# PCB_Tester2_V1_0.net
KiCad netlist of a schematic drawn in EAGLE
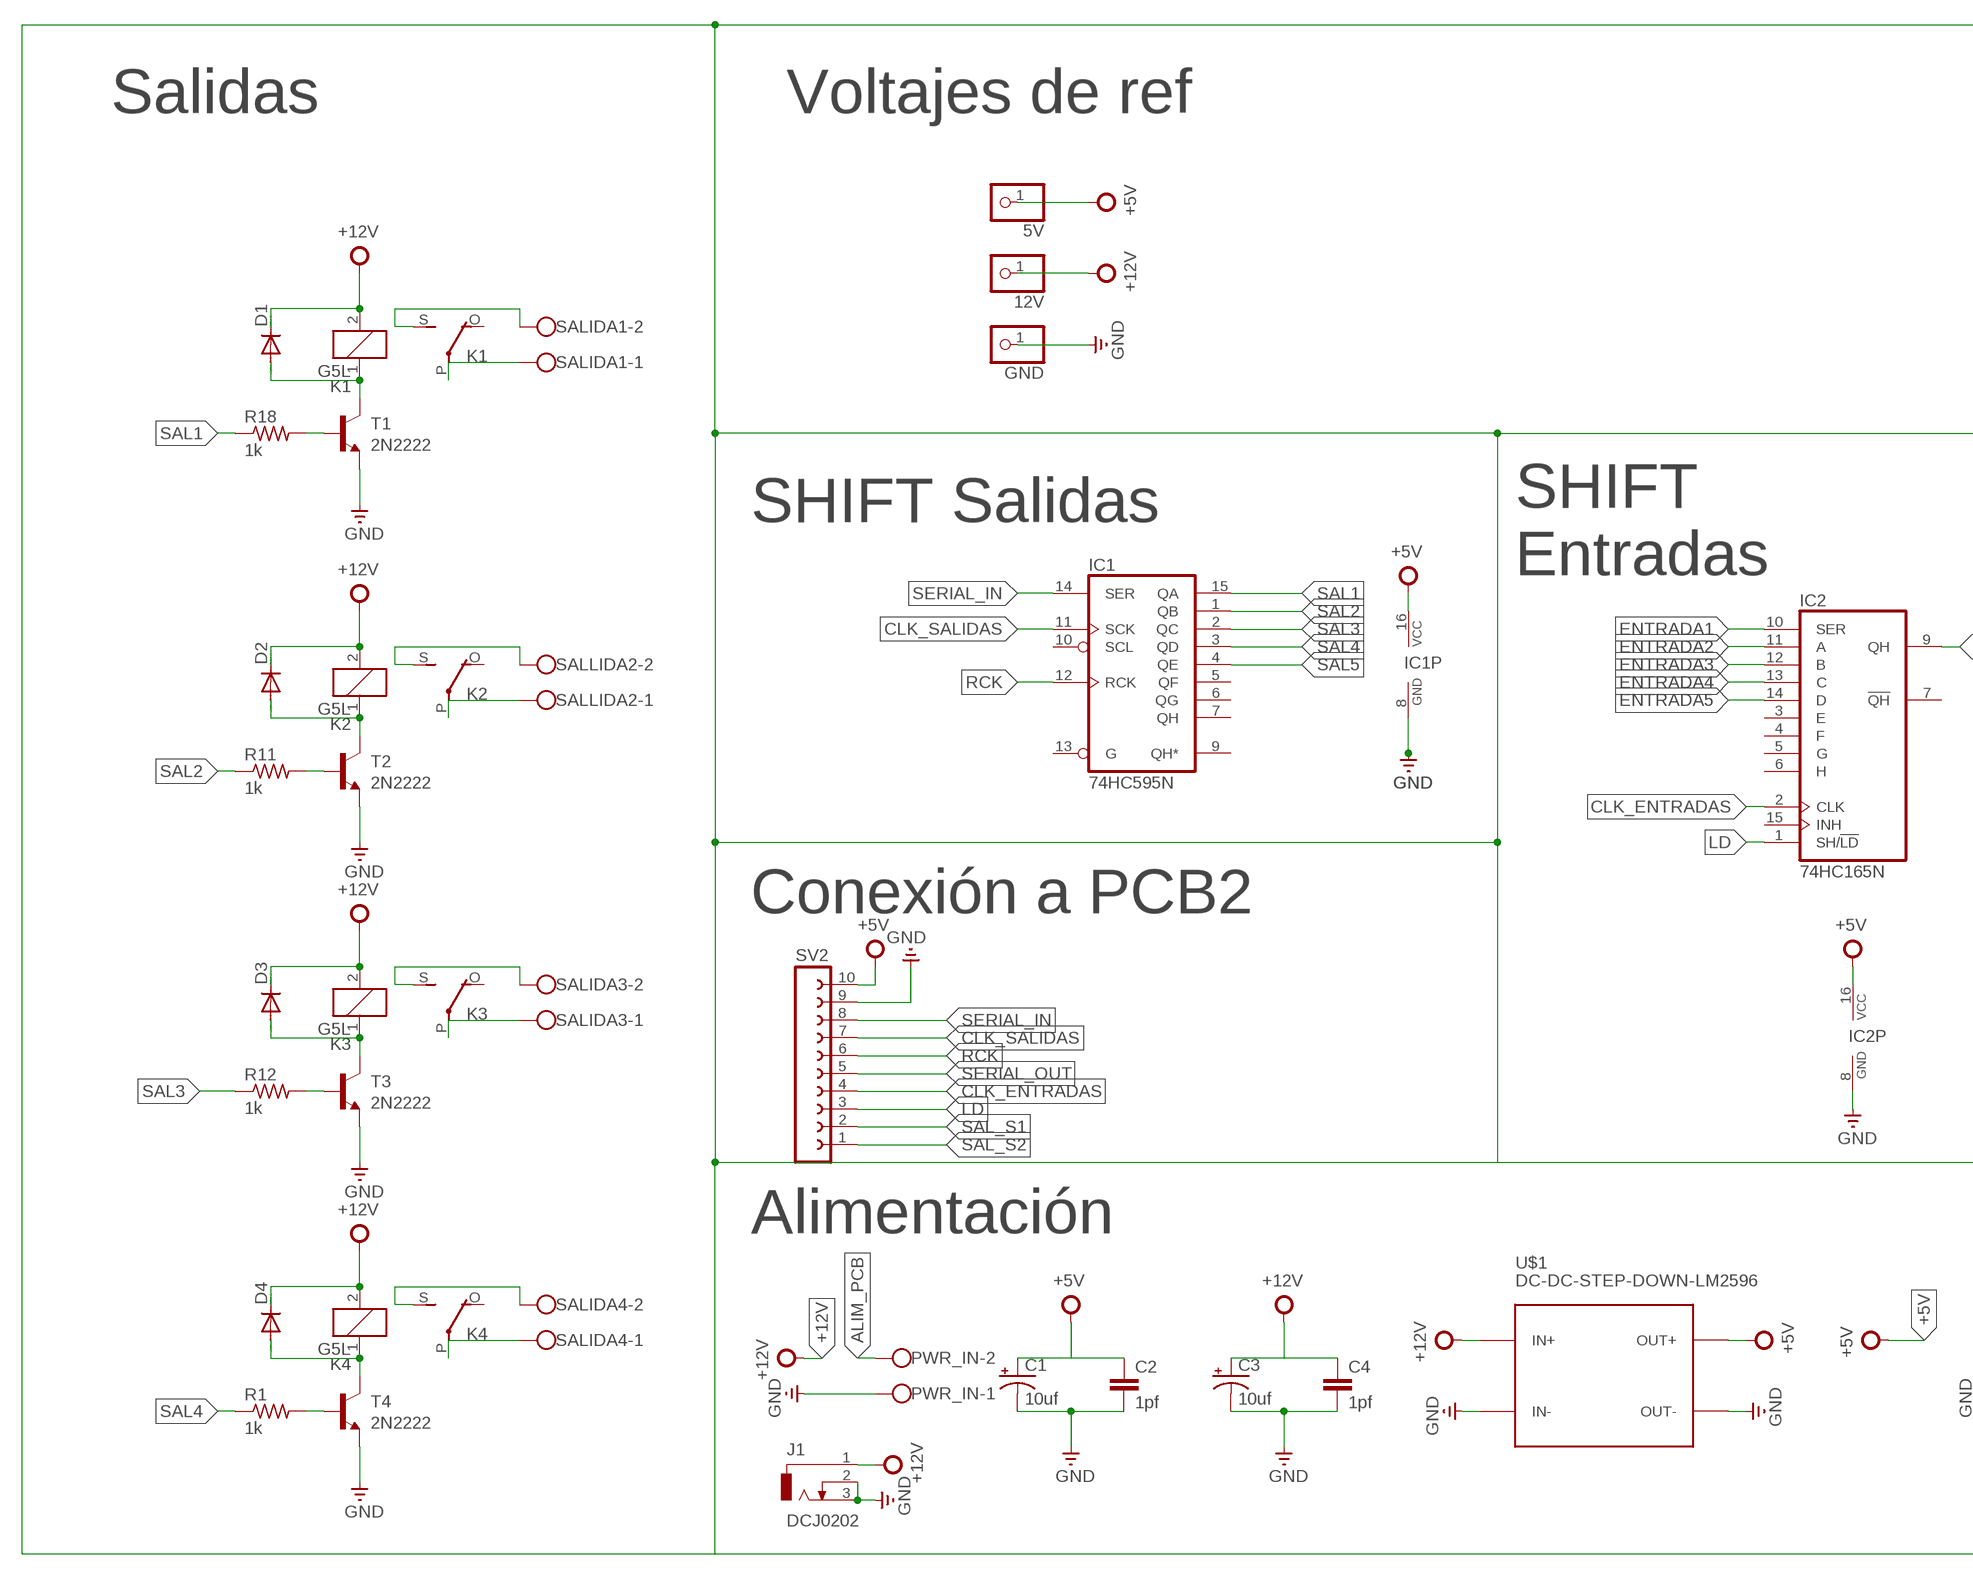
[diagram p0: schematic, sheet 1, part 1 of 2]
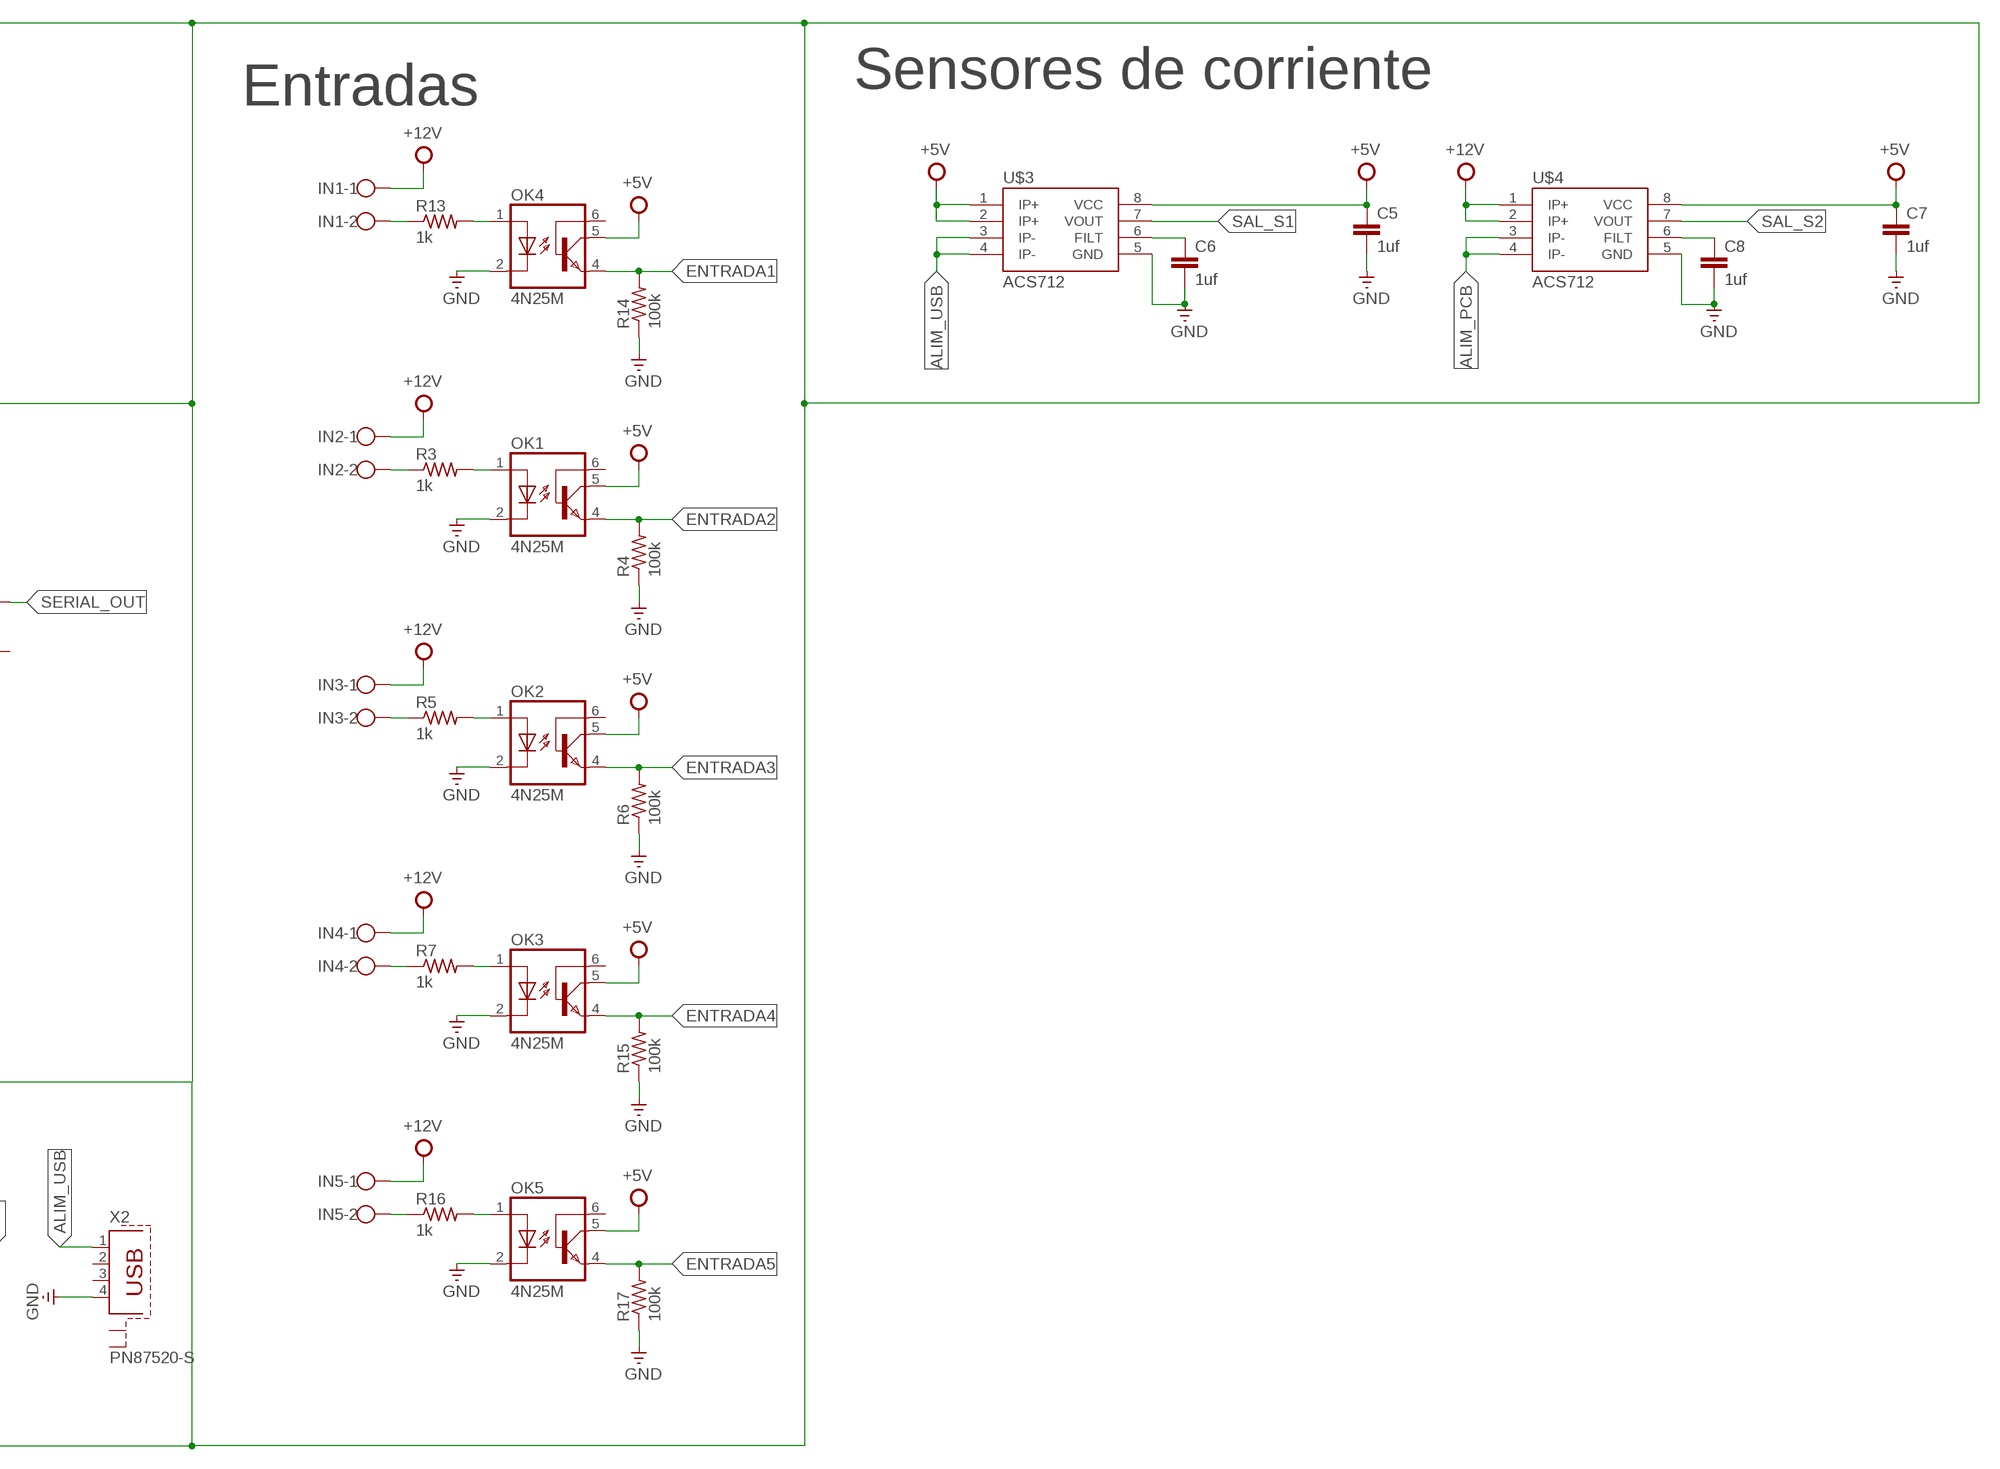
[diagram p1: schematic, sheet 1, part 2 of 2]

(export (version "E")
  (design (tool "Eeschema 10.0.6"))
  (components
    (comp (ref "5V")
      (value "PINHD-1X1")
      (footprint "eagle-import:1X01")
      (libsource (lib "eagle-import") (part "PINHD-1X1"))
    )
    (comp (ref "12V")
      (value "PINHD-1X1")
      (footprint "eagle-import:1X01")
      (libsource (lib "eagle-import") (part "PINHD-1X1"))
    )
    (comp (ref "C1")
      (value "10uf")
      (footprint "eagle-import:E2,5-6")
      (libsource (lib "eagle-import") (part "CPOL-USE2.5-6"))
    )
    (comp (ref "C2")
      (value "1pf")
      (footprint "eagle-import:C2.5-3")
      (libsource (lib "eagle-import") (part "C2,5-3"))
    )
    (comp (ref "C3")
      (value "10uf")
      (footprint "eagle-import:E2,5-6")
      (libsource (lib "eagle-import") (part "CPOL-USE2.5-6"))
    )
    (comp (ref "C4")
      (value "1pf")
      (footprint "eagle-import:C2.5-3")
      (libsource (lib "eagle-import") (part "C2,5-3"))
    )
    (comp (ref "C5")
      (value "1uf")
      (footprint "eagle-import:C2.5-3")
      (libsource (lib "eagle-import") (part "C2,5-3"))
    )
    (comp (ref "C6")
      (value "1uf")
      (footprint "eagle-import:C2.5-3")
      (libsource (lib "eagle-import") (part "C2,5-3"))
    )
    (comp (ref "C7")
      (value "1uf")
      (footprint "eagle-import:C2.5-3")
      (libsource (lib "eagle-import") (part "C2,5-3"))
    )
    (comp (ref "C8")
      (value "1uf")
      (footprint "eagle-import:C2.5-3")
      (libsource (lib "eagle-import") (part "C2,5-3"))
    )
    (comp (ref "D1")
      (value "1N4148DO35-7")
      (footprint "eagle-import:DO35-7")
      (libsource (lib "eagle-import") (part "1N4148DO35-7"))
    )
    (comp (ref "D2")
      (value "1N4148DO35-7")
      (footprint "eagle-import:DO35-7")
      (libsource (lib "eagle-import") (part "1N4148DO35-7"))
    )
    (comp (ref "D3")
      (value "1N4148DO35-7")
      (footprint "eagle-import:DO35-7")
      (libsource (lib "eagle-import") (part "1N4148DO35-7"))
    )
    (comp (ref "D4")
      (value "1N4148DO35-7")
      (footprint "eagle-import:DO35-7")
      (libsource (lib "eagle-import") (part "1N4148DO35-7"))
    )
    (comp (ref "GND")
      (value "PINHD-1X1")
      (footprint "eagle-import:1X01")
      (libsource (lib "eagle-import") (part "PINHD-1X1"))
    )
    (comp (ref "IC1")
      (value "74HC595N")
      (footprint "eagle-import:DIL16")
      (libsource (lib "eagle-import") (part "74595NHC"))
    )
    (comp (ref "IC2")
      (value "74HC165N")
      (footprint "eagle-import:DIL16")
      (libsource (lib "eagle-import") (part "74165NHC"))
    )
    (comp (ref "IN1")
      (value "W237-102")
      (footprint "eagle-import:W237-102")
      (fields (field (name "MPN") "237-102"))
      (libsource (lib "eagle-import") (part "W237-102"))
    )
    (comp (ref "IN2")
      (value "W237-102")
      (footprint "eagle-import:W237-102")
      (fields (field (name "MPN") "237-102"))
      (libsource (lib "eagle-import") (part "W237-102"))
    )
    (comp (ref "IN3")
      (value "W237-102")
      (footprint "eagle-import:W237-102")
      (fields (field (name "MPN") "237-102"))
      (libsource (lib "eagle-import") (part "W237-102"))
    )
    (comp (ref "IN4")
      (value "W237-102")
      (footprint "eagle-import:W237-102")
      (fields (field (name "MPN") "237-102"))
      (libsource (lib "eagle-import") (part "W237-102"))
    )
    (comp (ref "IN5")
      (value "W237-102")
      (footprint "eagle-import:W237-102")
      (fields (field (name "MPN") "237-102"))
      (libsource (lib "eagle-import") (part "W237-102"))
    )
    (comp (ref "J1")
      (value "DCJ0202")
      (footprint "eagle-import:DCJ0202")
      (libsource (lib "eagle-import") (part "DCJ0202"))
    )
    (comp (ref "K1")
      (value "G5L")
      (footprint "eagle-import:G5LE")
      (libsource (lib "eagle-import") (part "G5L"))
    )
    (comp (ref "K2")
      (value "G5L")
      (footprint "eagle-import:G5LE")
      (libsource (lib "eagle-import") (part "G5L"))
    )
    (comp (ref "K3")
      (value "G5L")
      (footprint "eagle-import:G5LE")
      (libsource (lib "eagle-import") (part "G5L"))
    )
    (comp (ref "K4")
      (value "G5L")
      (footprint "eagle-import:G5LE")
      (libsource (lib "eagle-import") (part "G5L"))
    )
    (comp (ref "OK1")
      (value "4N25M")
      (footprint "eagle-import:DIL06")
      (fields (field (name "MPN") "4N25-M"))
      (libsource (lib "eagle-import") (part "4N?M25"))
    )
    (comp (ref "OK2")
      (value "4N25M")
      (footprint "eagle-import:DIL06")
      (fields (field (name "MPN") "4N25-M"))
      (libsource (lib "eagle-import") (part "4N?M25"))
    )
    (comp (ref "OK3")
      (value "4N25M")
      (footprint "eagle-import:DIL06")
      (fields (field (name "MPN") "4N25-M"))
      (libsource (lib "eagle-import") (part "4N?M25"))
    )
    (comp (ref "OK4")
      (value "4N25M")
      (footprint "eagle-import:DIL06")
      (fields (field (name "MPN") "4N25-M"))
      (libsource (lib "eagle-import") (part "4N?M25"))
    )
    (comp (ref "OK5")
      (value "4N25M")
      (footprint "eagle-import:DIL06")
      (fields (field (name "MPN") "4N25-M"))
      (libsource (lib "eagle-import") (part "4N?M25"))
    )
    (comp (ref "PWR_IN")
      (value "W237-102")
      (footprint "eagle-import:W237-102")
      (fields (field (name "MPN") "237-102"))
      (libsource (lib "eagle-import") (part "W237-102"))
    )
    (comp (ref "R1")
      (value "1k")
      (footprint "eagle-import:0207_7")
      (libsource (lib "eagle-import") (part "R-US_0207/7"))
    )
    (comp (ref "R3")
      (value "1k")
      (footprint "eagle-import:0207_7")
      (libsource (lib "eagle-import") (part "R-US_0207/7"))
    )
    (comp (ref "R4")
      (value "100k")
      (footprint "eagle-import:0207_7")
      (libsource (lib "eagle-import") (part "R-US_0207/7"))
    )
    (comp (ref "R5")
      (value "1k")
      (footprint "eagle-import:0207_7")
      (libsource (lib "eagle-import") (part "R-US_0207/7"))
    )
    (comp (ref "R6")
      (value "100k")
      (footprint "eagle-import:0207_7")
      (libsource (lib "eagle-import") (part "R-US_0207/7"))
    )
    (comp (ref "R7")
      (value "1k")
      (footprint "eagle-import:0207_7")
      (libsource (lib "eagle-import") (part "R-US_0207/7"))
    )
    (comp (ref "R11")
      (value "1k")
      (footprint "eagle-import:0207_7")
      (libsource (lib "eagle-import") (part "R-US_0207/7"))
    )
    (comp (ref "R12")
      (value "1k")
      (footprint "eagle-import:0207_7")
      (libsource (lib "eagle-import") (part "R-US_0207/7"))
    )
    (comp (ref "R13")
      (value "1k")
      (footprint "eagle-import:0207_7")
      (libsource (lib "eagle-import") (part "R-US_0207/7"))
    )
    (comp (ref "R14")
      (value "100k")
      (footprint "eagle-import:0207_7")
      (libsource (lib "eagle-import") (part "R-US_0207/7"))
    )
    (comp (ref "R15")
      (value "100k")
      (footprint "eagle-import:0207_7")
      (libsource (lib "eagle-import") (part "R-US_0207/7"))
    )
    (comp (ref "R16")
      (value "1k")
      (footprint "eagle-import:0207_7")
      (libsource (lib "eagle-import") (part "R-US_0207/7"))
    )
    (comp (ref "R17")
      (value "100k")
      (footprint "eagle-import:0207_7")
      (libsource (lib "eagle-import") (part "R-US_0207/7"))
    )
    (comp (ref "R18")
      (value "1k")
      (footprint "eagle-import:0207_7")
      (libsource (lib "eagle-import") (part "R-US_0207/7"))
    )
    (comp (ref "SALIDA1")
      (value "W237-102")
      (footprint "eagle-import:W237-102")
      (fields (field (name "MPN") "237-102"))
      (libsource (lib "eagle-import") (part "W237-102"))
    )
    (comp (ref "SALIDA3")
      (value "W237-102")
      (footprint "eagle-import:W237-102")
      (fields (field (name "MPN") "237-102"))
      (libsource (lib "eagle-import") (part "W237-102"))
    )
    (comp (ref "SALIDA4")
      (value "W237-102")
      (footprint "eagle-import:W237-102")
      (fields (field (name "MPN") "237-102"))
      (libsource (lib "eagle-import") (part "W237-102"))
    )
    (comp (ref "SALLIDA2")
      (value "W237-102")
      (footprint "eagle-import:W237-102")
      (fields (field (name "MPN") "237-102"))
      (libsource (lib "eagle-import") (part "W237-102"))
    )
    (comp (ref "SV2")
      (value "FE10-1")
      (footprint "eagle-import:FE10")
      (libsource (lib "eagle-import") (part "FE10-1"))
    )
    (comp (ref "T1")
      (value "2N2222")
      (footprint "eagle-import:TO18")
      (libsource (lib "eagle-import") (part "2N2222"))
    )
    (comp (ref "T2")
      (value "2N2222")
      (footprint "eagle-import:TO18")
      (libsource (lib "eagle-import") (part "2N2222"))
    )
    (comp (ref "T3")
      (value "2N2222")
      (footprint "eagle-import:TO18")
      (libsource (lib "eagle-import") (part "2N2222"))
    )
    (comp (ref "T4")
      (value "2N2222")
      (footprint "eagle-import:TO18")
      (libsource (lib "eagle-import") (part "2N2222"))
    )
    (comp (ref "U$1")
      (value "DC-DC-STEP-DOWN-LM2596")
      (footprint "eagle-import:DC-DC-STEP-DOWN-LM2596")
      (libsource (lib "eagle-import") (part "DC-DC-STEP-DOWN-LM2596"))
    )
    (comp (ref "U$3")
      (value "ACS712")
      (footprint "eagle-import:SO08")
      (libsource (lib "eagle-import") (part "ACS712"))
    )
    (comp (ref "U$4")
      (value "ACS712")
      (footprint "eagle-import:SO08")
      (libsource (lib "eagle-import") (part "ACS712"))
    )
    (comp (ref "X2")
      (value "PN87520-S")
      (footprint "eagle-import:PN87520-S")
      (libsource (lib "eagle-import") (part "PN87520-S"))
    )
  )
  (nets
    (net (code "1") (name "+5V") (class "Default")
      (node (ref "5V") (pin "1") (pinfunction "1_1") (pintype "passive"))
      (node (ref "C1") (pin "+") (pinfunction "+_+") (pintype "passive"))
      (node (ref "C2") (pin "1") (pinfunction "1_1") (pintype "passive"))
      (node (ref "C5") (pin "1") (pinfunction "1_1") (pintype "passive"))
      (node (ref "C7") (pin "1") (pinfunction "1_1") (pintype "passive"))
      (node (ref "IC1") (pin "16") (pinfunction "VCC_16") (pintype "power_in"))
      (node (ref "IC2") (pin "16") (pinfunction "VCC_16") (pintype "power_in"))
      (node (ref "OK1") (pin "5") (pinfunction "COL_5") (pintype "passive"))
      (node (ref "OK2") (pin "5") (pinfunction "COL_5") (pintype "passive"))
      (node (ref "OK3") (pin "5") (pinfunction "COL_5") (pintype "passive"))
      (node (ref "OK4") (pin "5") (pinfunction "COL_5") (pintype "passive"))
      (node (ref "OK5") (pin "5") (pinfunction "COL_5") (pintype "passive"))
      (node (ref "SV2") (pin "10") (pinfunction "10_10") (pintype "passive"))
      (node (ref "U$1") (pin "OUT+") (pinfunction "OUT+_OUT+") (pintype "bidirectional"))
      (node (ref "U$3") (pin "1") (pinfunction "IP+_1") (pintype "bidirectional"))
      (node (ref "U$3") (pin "2") (pinfunction "IP+_2") (pintype "bidirectional"))
      (node (ref "U$3") (pin "8") (pinfunction "VCC_8") (pintype "bidirectional"))
      (node (ref "U$4") (pin "8") (pinfunction "VCC_8") (pintype "bidirectional"))
    )
    (net (code "2") (name "+12V") (class "Default")
      (node (ref "12V") (pin "1") (pinfunction "1_1") (pintype "passive"))
      (node (ref "C3") (pin "+") (pinfunction "+_+") (pintype "passive"))
      (node (ref "C4") (pin "1") (pinfunction "1_1") (pintype "passive"))
      (node (ref "D1") (pin "C") (pinfunction "C_C") (pintype "passive"))
      (node (ref "D2") (pin "C") (pinfunction "C_C") (pintype "passive"))
      (node (ref "D3") (pin "C") (pinfunction "C_C") (pintype "passive"))
      (node (ref "D4") (pin "C") (pinfunction "C_C") (pintype "passive"))
      (node (ref "IN1") (pin "1") (pinfunction "KL_1") (pintype "passive"))
      (node (ref "IN2") (pin "1") (pinfunction "KL_1") (pintype "passive"))
      (node (ref "IN3") (pin "1") (pinfunction "KL_1") (pintype "passive"))
      (node (ref "IN4") (pin "1") (pinfunction "KL_1") (pintype "passive"))
      (node (ref "IN5") (pin "1") (pinfunction "KL_1") (pintype "passive"))
      (node (ref "J1") (pin "1") (pinfunction "1_1") (pintype "passive"))
      (node (ref "K1") (pin "2") (pinfunction "2_2") (pintype "passive"))
      (node (ref "K2") (pin "2") (pinfunction "2_2") (pintype "passive"))
      (node (ref "K3") (pin "2") (pinfunction "2_2") (pintype "passive"))
      (node (ref "K4") (pin "2") (pinfunction "2_2") (pintype "passive"))
      (node (ref "U$1") (pin "IN+") (pinfunction "IN+_IN+") (pintype "bidirectional"))
      (node (ref "U$4") (pin "1") (pinfunction "IP+_1") (pintype "bidirectional"))
      (node (ref "U$4") (pin "2") (pinfunction "IP+_2") (pintype "bidirectional"))
    )
    (net (code "3") (name "ALIM_PCB") (class "Default")
      (node (ref "PWR_IN") (pin "2") (pinfunction "KL_2") (pintype "passive"))
      (node (ref "U$4") (pin "3") (pinfunction "IP-_3") (pintype "bidirectional"))
      (node (ref "U$4") (pin "4") (pinfunction "IP-_4") (pintype "bidirectional"))
    )
    (net (code "4") (name "ALIM_USB") (class "Default")
      (node (ref "U$3") (pin "3") (pinfunction "IP-_3") (pintype "bidirectional"))
      (node (ref "U$3") (pin "4") (pinfunction "IP-_4") (pintype "bidirectional"))
      (node (ref "X2") (pin "1") (pinfunction "1_1") (pintype "passive"))
    )
    (net (code "5") (name "CLK_ENTRADAS") (class "Default")
      (node (ref "IC2") (pin "2") (pinfunction "CLK_2") (pintype "input"))
      (node (ref "SV2") (pin "4") (pinfunction "4_4") (pintype "passive"))
    )
    (net (code "6") (name "CLK_SALIDAS") (class "Default")
      (node (ref "IC1") (pin "11") (pinfunction "SCK_11") (pintype "input"))
      (node (ref "SV2") (pin "7") (pinfunction "7_7") (pintype "passive"))
    )
    (net (code "7") (name "ENTRADA1") (class "Default")
      (node (ref "IC2") (pin "10") (pinfunction "SER_10") (pintype "input"))
      (node (ref "OK4") (pin "4") (pinfunction "EMI_4") (pintype "passive"))
      (node (ref "R14") (pin "2") (pinfunction "2_2") (pintype "passive"))
    )
    (net (code "8") (name "ENTRADA2") (class "Default")
      (node (ref "IC2") (pin "11") (pinfunction "A_11") (pintype "input"))
      (node (ref "OK1") (pin "4") (pinfunction "EMI_4") (pintype "passive"))
      (node (ref "R4") (pin "2") (pinfunction "2_2") (pintype "passive"))
    )
    (net (code "9") (name "ENTRADA3") (class "Default")
      (node (ref "IC2") (pin "12") (pinfunction "B_12") (pintype "input"))
      (node (ref "OK2") (pin "4") (pinfunction "EMI_4") (pintype "passive"))
      (node (ref "R6") (pin "2") (pinfunction "2_2") (pintype "passive"))
    )
    (net (code "10") (name "ENTRADA4") (class "Default")
      (node (ref "IC2") (pin "13") (pinfunction "C_13") (pintype "input"))
      (node (ref "OK3") (pin "4") (pinfunction "EMI_4") (pintype "passive"))
      (node (ref "R15") (pin "2") (pinfunction "2_2") (pintype "passive"))
    )
    (net (code "11") (name "ENTRADA5") (class "Default")
      (node (ref "IC2") (pin "14") (pinfunction "D_14") (pintype "input"))
      (node (ref "OK5") (pin "4") (pinfunction "EMI_4") (pintype "passive"))
      (node (ref "R17") (pin "2") (pinfunction "2_2") (pintype "passive"))
    )
    (net (code "12") (name "GND") (class "Default")
      (node (ref "C1") (pin "-") (pinfunction "-_-") (pintype "passive"))
      (node (ref "C2") (pin "2") (pinfunction "2_2") (pintype "passive"))
      (node (ref "C3") (pin "-") (pinfunction "-_-") (pintype "passive"))
      (node (ref "C4") (pin "2") (pinfunction "2_2") (pintype "passive"))
      (node (ref "C5") (pin "2") (pinfunction "2_2") (pintype "passive"))
      (node (ref "C6") (pin "2") (pinfunction "2_2") (pintype "passive"))
      (node (ref "C7") (pin "2") (pinfunction "2_2") (pintype "passive"))
      (node (ref "C8") (pin "2") (pinfunction "2_2") (pintype "passive"))
      (node (ref "GND") (pin "1") (pinfunction "1_1") (pintype "passive"))
      (node (ref "IC1") (pin "8") (pinfunction "GND_8") (pintype "power_in"))
      (node (ref "IC2") (pin "8") (pinfunction "GND_8") (pintype "power_in"))
      (node (ref "J1") (pin "2") (pinfunction "2_2") (pintype "passive"))
      (node (ref "J1") (pin "3") (pinfunction "3_3") (pintype "passive"))
      (node (ref "OK1") (pin "2") (pinfunction "C_2") (pintype "passive"))
      (node (ref "OK2") (pin "2") (pinfunction "C_2") (pintype "passive"))
      (node (ref "OK3") (pin "2") (pinfunction "C_2") (pintype "passive"))
      (node (ref "OK4") (pin "2") (pinfunction "C_2") (pintype "passive"))
      (node (ref "OK5") (pin "2") (pinfunction "C_2") (pintype "passive"))
      (node (ref "PWR_IN") (pin "1") (pinfunction "KL_1") (pintype "passive"))
      (node (ref "R14") (pin "1") (pinfunction "1_1") (pintype "passive"))
      (node (ref "R15") (pin "1") (pinfunction "1_1") (pintype "passive"))
      (node (ref "R17") (pin "1") (pinfunction "1_1") (pintype "passive"))
      (node (ref "R4") (pin "1") (pinfunction "1_1") (pintype "passive"))
      (node (ref "R6") (pin "1") (pinfunction "1_1") (pintype "passive"))
      (node (ref "SV2") (pin "9") (pinfunction "9_9") (pintype "passive"))
      (node (ref "T1") (pin "1") (pinfunction "E_1") (pintype "passive"))
      (node (ref "T2") (pin "1") (pinfunction "E_1") (pintype "passive"))
      (node (ref "T3") (pin "1") (pinfunction "E_1") (pintype "passive"))
      (node (ref "T4") (pin "1") (pinfunction "E_1") (pintype "passive"))
      (node (ref "U$1") (pin "IN-") (pinfunction "IN-_IN-") (pintype "bidirectional"))
      (node (ref "U$1") (pin "OUT-") (pinfunction "OUT-_OUT-") (pintype "bidirectional"))
      (node (ref "U$3") (pin "5") (pinfunction "GND_5") (pintype "bidirectional"))
      (node (ref "U$4") (pin "5") (pinfunction "GND_5") (pintype "bidirectional"))
      (node (ref "X2") (pin "4") (pinfunction "4_4") (pintype "passive"))
    )
    (net (code "13") (name "LD") (class "Default")
      (node (ref "IC2") (pin "1") (pinfunction "SH/~{LD}_1") (pintype "input"))
      (node (ref "SV2") (pin "3") (pinfunction "3_3") (pintype "passive"))
    )
    (net (code "14") (name "Net-(IN1B-KL)") (class "Default")
      (node (ref "IN1") (pin "2") (pinfunction "KL_2") (pintype "passive"))
      (node (ref "R13") (pin "1") (pinfunction "1_1") (pintype "passive"))
    )
    (net (code "15") (name "Net-(IN2B-KL)") (class "Default")
      (node (ref "IN2") (pin "2") (pinfunction "KL_2") (pintype "passive"))
      (node (ref "R3") (pin "1") (pinfunction "1_1") (pintype "passive"))
    )
    (net (code "16") (name "Net-(IN3B-KL)") (class "Default")
      (node (ref "IN3") (pin "2") (pinfunction "KL_2") (pintype "passive"))
      (node (ref "R5") (pin "1") (pinfunction "1_1") (pintype "passive"))
    )
    (net (code "17") (name "Net-(IN4B-KL)") (class "Default")
      (node (ref "IN4") (pin "2") (pinfunction "KL_2") (pintype "passive"))
      (node (ref "R7") (pin "1") (pinfunction "1_1") (pintype "passive"))
    )
    (net (code "18") (name "Net-(IN5B-KL)") (class "Default")
      (node (ref "IN5") (pin "2") (pinfunction "KL_2") (pintype "passive"))
      (node (ref "R16") (pin "1") (pinfunction "1_1") (pintype "passive"))
    )
    (net (code "19") (name "Net-(OK1-A)") (class "Default")
      (node (ref "OK1") (pin "1") (pinfunction "A_1") (pintype "passive"))
      (node (ref "R3") (pin "2") (pinfunction "2_2") (pintype "passive"))
    )
    (net (code "20") (name "Net-(OK2-A)") (class "Default")
      (node (ref "OK2") (pin "1") (pinfunction "A_1") (pintype "passive"))
      (node (ref "R5") (pin "2") (pinfunction "2_2") (pintype "passive"))
    )
    (net (code "21") (name "Net-(OK3-A)") (class "Default")
      (node (ref "OK3") (pin "1") (pinfunction "A_1") (pintype "passive"))
      (node (ref "R7") (pin "2") (pinfunction "2_2") (pintype "passive"))
    )
    (net (code "22") (name "Net-(OK4-A)") (class "Default")
      (node (ref "OK4") (pin "1") (pinfunction "A_1") (pintype "passive"))
      (node (ref "R13") (pin "2") (pinfunction "2_2") (pintype "passive"))
    )
    (net (code "23") (name "Net-(OK5-A)") (class "Default")
      (node (ref "OK5") (pin "1") (pinfunction "A_1") (pintype "passive"))
      (node (ref "R16") (pin "2") (pinfunction "2_2") (pintype "passive"))
    )
    (net (code "24") (name "Net-(SALIDA1A-KL)") (class "Default")
      (node (ref "K1") (pin "P") (pinfunction "P_P") (pintype "passive"))
      (node (ref "SALIDA1") (pin "1") (pinfunction "KL_1") (pintype "passive"))
    )
    (net (code "25") (name "Net-(SALIDA1B-KL)") (class "Default")
      (node (ref "K1") (pin "S") (pinfunction "S_S") (pintype "passive"))
      (node (ref "SALIDA1") (pin "2") (pinfunction "KL_2") (pintype "passive"))
    )
    (net (code "26") (name "Net-(SALIDA3A-KL)") (class "Default")
      (node (ref "K3") (pin "P") (pinfunction "P_P") (pintype "passive"))
      (node (ref "SALIDA3") (pin "1") (pinfunction "KL_1") (pintype "passive"))
    )
    (net (code "27") (name "Net-(SALIDA3B-KL)") (class "Default")
      (node (ref "K3") (pin "S") (pinfunction "S_S") (pintype "passive"))
      (node (ref "SALIDA3") (pin "2") (pinfunction "KL_2") (pintype "passive"))
    )
    (net (code "28") (name "Net-(SALIDA4A-KL)") (class "Default")
      (node (ref "K4") (pin "P") (pinfunction "P_P") (pintype "passive"))
      (node (ref "SALIDA4") (pin "1") (pinfunction "KL_1") (pintype "passive"))
    )
    (net (code "29") (name "Net-(SALIDA4B-KL)") (class "Default")
      (node (ref "K4") (pin "S") (pinfunction "S_S") (pintype "passive"))
      (node (ref "SALIDA4") (pin "2") (pinfunction "KL_2") (pintype "passive"))
    )
    (net (code "30") (name "Net-(SALLIDA2A-KL)") (class "Default")
      (node (ref "K2") (pin "P") (pinfunction "P_P") (pintype "passive"))
      (node (ref "SALLIDA2") (pin "1") (pinfunction "KL_1") (pintype "passive"))
    )
    (net (code "31") (name "Net-(SALLIDA2B-KL)") (class "Default")
      (node (ref "K2") (pin "S") (pinfunction "S_S") (pintype "passive"))
      (node (ref "SALLIDA2") (pin "2") (pinfunction "KL_2") (pintype "passive"))
    )
    (net (code "32") (name "Net-(T1-B)") (class "Default")
      (node (ref "R18") (pin "2") (pinfunction "2_2") (pintype "passive"))
      (node (ref "T1") (pin "2") (pinfunction "B_2") (pintype "passive"))
    )
    (net (code "33") (name "Net-(T1-C)") (class "Default")
      (node (ref "D1") (pin "A") (pinfunction "A_A") (pintype "passive"))
      (node (ref "K1") (pin "1") (pinfunction "1_1") (pintype "passive"))
      (node (ref "T1") (pin "3") (pinfunction "C_3") (pintype "passive"))
    )
    (net (code "34") (name "Net-(T2-B)") (class "Default")
      (node (ref "R11") (pin "2") (pinfunction "2_2") (pintype "passive"))
      (node (ref "T2") (pin "2") (pinfunction "B_2") (pintype "passive"))
    )
    (net (code "35") (name "Net-(T2-C)") (class "Default")
      (node (ref "D2") (pin "A") (pinfunction "A_A") (pintype "passive"))
      (node (ref "K2") (pin "1") (pinfunction "1_1") (pintype "passive"))
      (node (ref "T2") (pin "3") (pinfunction "C_3") (pintype "passive"))
    )
    (net (code "36") (name "Net-(T3-B)") (class "Default")
      (node (ref "R12") (pin "2") (pinfunction "2_2") (pintype "passive"))
      (node (ref "T3") (pin "2") (pinfunction "B_2") (pintype "passive"))
    )
    (net (code "37") (name "Net-(T3-C)") (class "Default")
      (node (ref "D3") (pin "A") (pinfunction "A_A") (pintype "passive"))
      (node (ref "K3") (pin "1") (pinfunction "1_1") (pintype "passive"))
      (node (ref "T3") (pin "3") (pinfunction "C_3") (pintype "passive"))
    )
    (net (code "38") (name "Net-(T4-B)") (class "Default")
      (node (ref "R1") (pin "2") (pinfunction "2_2") (pintype "passive"))
      (node (ref "T4") (pin "2") (pinfunction "B_2") (pintype "passive"))
    )
    (net (code "39") (name "Net-(T4-C)") (class "Default")
      (node (ref "D4") (pin "A") (pinfunction "A_A") (pintype "passive"))
      (node (ref "K4") (pin "1") (pinfunction "1_1") (pintype "passive"))
      (node (ref "T4") (pin "3") (pinfunction "C_3") (pintype "passive"))
    )
    (net (code "40") (name "Net-(U$3-FILT)") (class "Default")
      (node (ref "C6") (pin "1") (pinfunction "1_1") (pintype "passive"))
      (node (ref "U$3") (pin "6") (pinfunction "FILT_6") (pintype "bidirectional"))
    )
    (net (code "41") (name "Net-(U$4-FILT)") (class "Default")
      (node (ref "C8") (pin "1") (pinfunction "1_1") (pintype "passive"))
      (node (ref "U$4") (pin "6") (pinfunction "FILT_6") (pintype "bidirectional"))
    )
    (net (code "42") (name "RCK") (class "Default")
      (node (ref "IC1") (pin "12") (pinfunction "RCK_12") (pintype "input"))
      (node (ref "SV2") (pin "6") (pinfunction "6_6") (pintype "passive"))
    )
    (net (code "43") (name "SAL1") (class "Default")
      (node (ref "IC1") (pin "15") (pinfunction "QA_15") (pintype "tri_state"))
      (node (ref "R18") (pin "1") (pinfunction "1_1") (pintype "passive"))
    )
    (net (code "44") (name "SAL2") (class "Default")
      (node (ref "IC1") (pin "1") (pinfunction "QB_1") (pintype "tri_state"))
      (node (ref "R11") (pin "1") (pinfunction "1_1") (pintype "passive"))
    )
    (net (code "45") (name "SAL3") (class "Default")
      (node (ref "IC1") (pin "2") (pinfunction "QC_2") (pintype "tri_state"))
      (node (ref "R12") (pin "1") (pinfunction "1_1") (pintype "passive"))
    )
    (net (code "46") (name "SAL4") (class "Default")
      (node (ref "IC1") (pin "3") (pinfunction "QD_3") (pintype "tri_state"))
      (node (ref "R1") (pin "1") (pinfunction "1_1") (pintype "passive"))
    )
    (net (code "47") (name "SAL5") (class "Default")
      (node (ref "IC1") (pin "4") (pinfunction "QE_4") (pintype "tri_state"))
    )
    (net (code "48") (name "SAL_S1") (class "Default")
      (node (ref "SV2") (pin "2") (pinfunction "2_2") (pintype "passive"))
      (node (ref "U$3") (pin "7") (pinfunction "VOUT_7") (pintype "bidirectional"))
    )
    (net (code "49") (name "SAL_S2") (class "Default")
      (node (ref "SV2") (pin "1") (pinfunction "1_1") (pintype "passive"))
      (node (ref "U$4") (pin "7") (pinfunction "VOUT_7") (pintype "bidirectional"))
    )
    (net (code "50") (name "SERIAL_IN") (class "Default")
      (node (ref "IC1") (pin "14") (pinfunction "SER_14") (pintype "input"))
      (node (ref "SV2") (pin "8") (pinfunction "8_8") (pintype "passive"))
    )
    (net (code "51") (name "SERIAL_OUT") (class "Default")
      (node (ref "IC2") (pin "9") (pinfunction "QH_9") (pintype "output"))
      (node (ref "SV2") (pin "5") (pinfunction "5_5") (pintype "passive"))
    )
    (net (code "52") (name "unconnected-(IC1A-G-Pad13)") (class "Default")
      (node (ref "IC1") (pin "13") (pinfunction "G_13") (pintype "input"))
    )
    (net (code "53") (name "unconnected-(IC1A-QF-Pad5)") (class "Default")
      (node (ref "IC1") (pin "5") (pinfunction "QF_5") (pintype "tri_state"))
    )
    (net (code "54") (name "unconnected-(IC1A-QG-Pad6)") (class "Default")
      (node (ref "IC1") (pin "6") (pinfunction "QG_6") (pintype "tri_state"))
    )
    (net (code "55") (name "unconnected-(IC1A-QH*-Pad9)") (class "Default")
      (node (ref "IC1") (pin "9") (pinfunction "QH*_9") (pintype "tri_state"))
    )
    (net (code "56") (name "unconnected-(IC1A-QH-Pad7)") (class "Default")
      (node (ref "IC1") (pin "7") (pinfunction "QH_7") (pintype "tri_state"))
    )
    (net (code "57") (name "unconnected-(IC1A-SCL-Pad10)") (class "Default")
      (node (ref "IC1") (pin "10") (pinfunction "SCL_10") (pintype "input"))
    )
    (net (code "58") (name "unconnected-(IC2A-E-Pad3)") (class "Default")
      (node (ref "IC2") (pin "3") (pinfunction "E_3") (pintype "input"))
    )
    (net (code "59") (name "unconnected-(IC2A-F-Pad4)") (class "Default")
      (node (ref "IC2") (pin "4") (pinfunction "F_4") (pintype "input"))
    )
    (net (code "60") (name "unconnected-(IC2A-G-Pad5)") (class "Default")
      (node (ref "IC2") (pin "5") (pinfunction "G_5") (pintype "input"))
    )
    (net (code "61") (name "unconnected-(IC2A-H-Pad6)") (class "Default")
      (node (ref "IC2") (pin "6") (pinfunction "H_6") (pintype "input"))
    )
    (net (code "62") (name "unconnected-(IC2A-INH-Pad15)") (class "Default")
      (node (ref "IC2") (pin "15") (pinfunction "INH_15") (pintype "input"))
    )
    (net (code "63") (name "unconnected-(IC2A-~{QH}-Pad7)") (class "Default")
      (node (ref "IC2") (pin "7") (pinfunction "~{QH}_7") (pintype "output"))
    )
    (net (code "64") (name "unconnected-(K1-PadO)") (class "Default")
      (node (ref "K1") (pin "O") (pinfunction "O_O") (pintype "passive"))
    )
    (net (code "65") (name "unconnected-(K2-PadO)") (class "Default")
      (node (ref "K2") (pin "O") (pinfunction "O_O") (pintype "passive"))
    )
    (net (code "66") (name "unconnected-(K3-PadO)") (class "Default")
      (node (ref "K3") (pin "O") (pinfunction "O_O") (pintype "passive"))
    )
    (net (code "67") (name "unconnected-(K4-PadO)") (class "Default")
      (node (ref "K4") (pin "O") (pinfunction "O_O") (pintype "passive"))
    )
    (net (code "68") (name "unconnected-(OK1-BAS-Pad6)") (class "Default")
      (node (ref "OK1") (pin "6") (pinfunction "BAS_6") (pintype "passive"))
    )
    (net (code "69") (name "unconnected-(OK2-BAS-Pad6)") (class "Default")
      (node (ref "OK2") (pin "6") (pinfunction "BAS_6") (pintype "passive"))
    )
    (net (code "70") (name "unconnected-(OK3-BAS-Pad6)") (class "Default")
      (node (ref "OK3") (pin "6") (pinfunction "BAS_6") (pintype "passive"))
    )
    (net (code "71") (name "unconnected-(OK4-BAS-Pad6)") (class "Default")
      (node (ref "OK4") (pin "6") (pinfunction "BAS_6") (pintype "passive"))
    )
    (net (code "72") (name "unconnected-(OK5-BAS-Pad6)") (class "Default")
      (node (ref "OK5") (pin "6") (pinfunction "BAS_6") (pintype "passive"))
    )
    (net (code "73") (name "unconnected-(X2-Pad2)") (class "Default")
      (node (ref "X2") (pin "2") (pinfunction "2_2") (pintype "passive"))
    )
    (net (code "74") (name "unconnected-(X2-Pad3)") (class "Default")
      (node (ref "X2") (pin "3") (pinfunction "3_3") (pintype "passive"))
    )
    (net (code "75") (name "unconnected-(X2-PadS1)") (class "Default")
      (node (ref "X2") (pin "S1") (pinfunction "S1_S1") (pintype "passive"))
    )
    (net (code "76") (name "unconnected-(X2-PadS2)") (class "Default")
      (node (ref "X2") (pin "S2") (pinfunction "S2_S2") (pintype "passive"))
    )
  )
)
